# brush.net
KiCad netlist of a schematic drawn in EAGLE
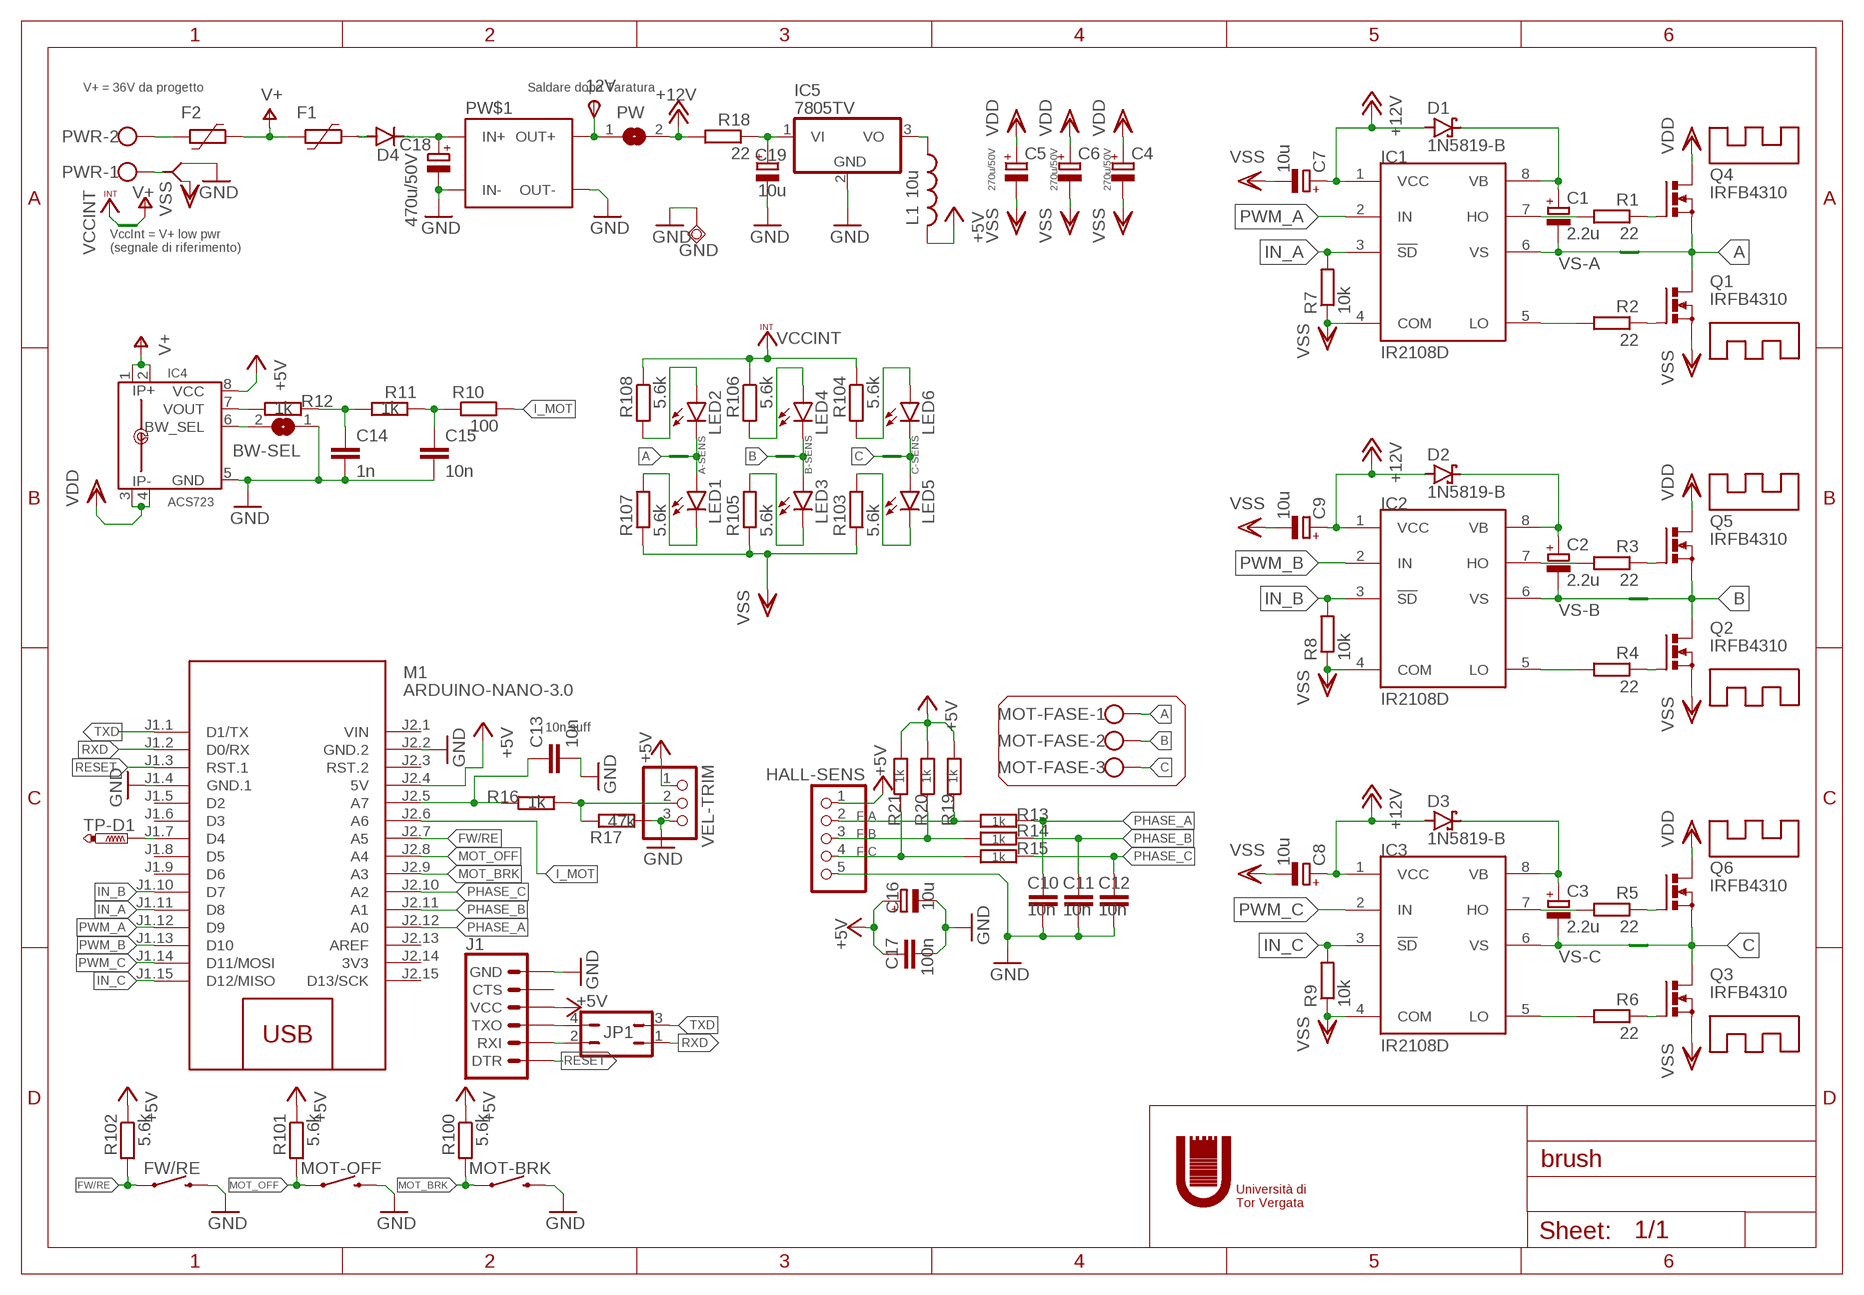
[diagram p0: schematic, sheet 1]

(export (version "E")
  (design (tool "Eeschema 10.0.6"))
  (components
    (comp (ref "12V")
      (value "TPSPAD1-13")
      (footprint "eagle-import:P1-13")
      (libsource (lib "eagle-import") (part "TPSPAD1-13"))
    )
    (comp (ref "BW-SEL")
      (value "SJ")
      (footprint "eagle-import:SJ")
      (libsource (lib "eagle-import") (part "SJ"))
    )
    (comp (ref "C1")
      (value "2.2u")
      (footprint "eagle-import:E5-6")
      (libsource (lib "eagle-import") (part "CPOL-EUE5-6"))
    )
    (comp (ref "C2")
      (value "2.2u")
      (footprint "eagle-import:E5-6")
      (libsource (lib "eagle-import") (part "CPOL-EUE5-6"))
    )
    (comp (ref "C3")
      (value "2.2u")
      (footprint "eagle-import:E5-6")
      (libsource (lib "eagle-import") (part "CPOL-EUE5-6"))
    )
    (comp (ref "C4")
      (value "270u/50V")
      (footprint "eagle-import:E7,5-18")
      (libsource (lib "eagle-import") (part "CPOL-EUE7.5-18"))
    )
    (comp (ref "C5")
      (value "270u/50V")
      (footprint "eagle-import:E7,5-18")
      (libsource (lib "eagle-import") (part "CPOL-EUE7.5-18"))
    )
    (comp (ref "C6")
      (value "270u/50V")
      (footprint "eagle-import:E7,5-18")
      (libsource (lib "eagle-import") (part "CPOL-EUE7.5-18"))
    )
    (comp (ref "C7")
      (value "10u")
      (footprint "eagle-import:E5-6")
      (libsource (lib "eagle-import") (part "CPOL-EUE5-6"))
    )
    (comp (ref "C8")
      (value "10u")
      (footprint "eagle-import:E5-6")
      (libsource (lib "eagle-import") (part "CPOL-EUE5-6"))
    )
    (comp (ref "C9")
      (value "10u")
      (footprint "eagle-import:E5-6")
      (libsource (lib "eagle-import") (part "CPOL-EUE5-6"))
    )
    (comp (ref "C10")
      (value "10n")
      (footprint "eagle-import:C025-025X050")
      (libsource (lib "eagle-import") (part "C-EU025-025X050"))
    )
    (comp (ref "C11")
      (value "10n")
      (footprint "eagle-import:C025-025X050")
      (libsource (lib "eagle-import") (part "C-EU025-025X050"))
    )
    (comp (ref "C12")
      (value "10n")
      (footprint "eagle-import:C025-025X050")
      (libsource (lib "eagle-import") (part "C-EU025-025X050"))
    )
    (comp (ref "C13")
      (value "10n")
      (footprint "eagle-import:C025-025X050")
      (libsource (lib "eagle-import") (part "C-EU025-025X050"))
    )
    (comp (ref "C14")
      (value "1n")
      (footprint "eagle-import:C025-025X050")
      (libsource (lib "eagle-import") (part "C-EU025-025X050"))
    )
    (comp (ref "C15")
      (value "10n")
      (footprint "eagle-import:C025-025X050")
      (libsource (lib "eagle-import") (part "C-EU025-025X050"))
    )
    (comp (ref "C16")
      (value "10u")
      (footprint "eagle-import:E5-6")
      (libsource (lib "eagle-import") (part "CPOL-EUE5-6"))
    )
    (comp (ref "C17")
      (value "100n")
      (footprint "eagle-import:C025-025X050")
      (libsource (lib "eagle-import") (part "C-EU025-025X050"))
    )
    (comp (ref "C18")
      (value "470u/50V")
      (footprint "eagle-import:E5-13")
      (libsource (lib "eagle-import") (part "CPOL-EUE5-13"))
    )
    (comp (ref "C19")
      (value "10u")
      (footprint "eagle-import:E5-6")
      (libsource (lib "eagle-import") (part "CPOL-EUE5-6"))
    )
    (comp (ref "D1")
      (value "1N5819-B")
      (footprint "eagle-import:DO41-7.6")
      (libsource (lib "eagle-import") (part "1N5819-B"))
    )
    (comp (ref "D2")
      (value "1N5819-B")
      (footprint "eagle-import:DO41-7.6")
      (libsource (lib "eagle-import") (part "1N5819-B"))
    )
    (comp (ref "D3")
      (value "1N5819-B")
      (footprint "eagle-import:DO41-7.6")
      (libsource (lib "eagle-import") (part "1N5819-B"))
    )
    (comp (ref "D4")
      (value "ES2D")
      (footprint "eagle-import:SMB")
      (libsource (lib "eagle-import") (part "ES2D"))
    )
    (comp (ref "F1")
      (value "2410-BOX")
      (footprint "eagle-import:BELFUSE0679-3000-12")
      (libsource (lib "eagle-import") (part "?2410-BOX"))
    )
    (comp (ref "F2")
      (value "2410-BOX")
      (footprint "eagle-import:BELFUSE0679-3000-12")
      (libsource (lib "eagle-import") (part "?2410-BOX"))
    )
    (comp (ref "FW/RE")
      (value "MOMENTARY-SWITCH-SPST-PTH-6.0MM")
      (footprint "eagle-import:TACTILE_SWITCH_PTH_6.0MM")
      (libsource (lib "eagle-import") (part "MOMENTARY-SWITCH-SPST-PTH-6.0MM"))
    )
    (comp (ref "GND")
      (value "TPSQPAD1-13")
      (footprint "eagle-import:P1-13")
      (libsource (lib "eagle-import") (part "TPSQPAD1-13"))
    )
    (comp (ref "HALL-SENS")
      (value "PINHD-1X5")
      (footprint "eagle-import:1X05")
      (libsource (lib "eagle-import") (part "PINHD-1X5"))
    )
    (comp (ref "IC1")
      (value "IR2108D")
      (footprint "eagle-import:DIL08")
      (libsource (lib "eagle-import") (part "IR2108D"))
    )
    (comp (ref "IC2")
      (value "IR2108D")
      (footprint "eagle-import:DIL08")
      (libsource (lib "eagle-import") (part "IR2108D"))
    )
    (comp (ref "IC3")
      (value "IR2108D")
      (footprint "eagle-import:DIL08")
      (libsource (lib "eagle-import") (part "IR2108D"))
    )
    (comp (ref "IC4")
      (value "ACS723")
      (footprint "eagle-import:SOIC8")
      (libsource (lib "eagle-import") (part "ACS723"))
    )
    (comp (ref "IC5")
      (value "7805TV")
      (footprint "eagle-import:TO220V")
      (libsource (lib "eagle-import") (part "78TV05"))
    )
    (comp (ref "J1")
      (value "6_PIN_SERIAL_TARGETSILK")
      (footprint "eagle-import:6_PIN_SERIAL_TARGET_SIDE_W_SILK")
      (libsource (lib "eagle-import") (part "6_PIN_SERIAL_TARGETSILK"))
    )
    (comp (ref "JP1")
      (value "JP2Q")
      (footprint "eagle-import:JP2Q")
      (libsource (lib "eagle-import") (part "JP2Q"))
    )
    (comp (ref "L1")
      (value "10u")
      (footprint "eagle-import:0207_5V")
      (libsource (lib "eagle-import") (part "L-US0207/5V"))
    )
    (comp (ref "LED1")
      (value "LED3MM")
      (footprint "eagle-import:LED3MM")
      (libsource (lib "eagle-import") (part "LED3MM"))
    )
    (comp (ref "LED2")
      (value "LED3MM")
      (footprint "eagle-import:LED3MM")
      (libsource (lib "eagle-import") (part "LED3MM"))
    )
    (comp (ref "LED3")
      (value "LED3MM")
      (footprint "eagle-import:LED3MM")
      (libsource (lib "eagle-import") (part "LED3MM"))
    )
    (comp (ref "LED4")
      (value "LED3MM")
      (footprint "eagle-import:LED3MM")
      (libsource (lib "eagle-import") (part "LED3MM"))
    )
    (comp (ref "LED5")
      (value "LED3MM")
      (footprint "eagle-import:LED3MM")
      (libsource (lib "eagle-import") (part "LED3MM"))
    )
    (comp (ref "LED6")
      (value "LED3MM")
      (footprint "eagle-import:LED3MM")
      (libsource (lib "eagle-import") (part "LED3MM"))
    )
    (comp (ref "M1")
      (value "ARDUINO-NANO-3.0")
      (footprint "eagle-import:ARDUINO-NANO-3.0")
      (libsource (lib "eagle-import") (part "ARDUINO-NANO-3.0"))
    )
    (comp (ref "MOT-BRK")
      (value "MOMENTARY-SWITCH-SPST-PTH-6.0MM")
      (footprint "eagle-import:TACTILE_SWITCH_PTH_6.0MM")
      (libsource (lib "eagle-import") (part "MOMENTARY-SWITCH-SPST-PTH-6.0MM"))
    )
    (comp (ref "MOT-FASE")
      (value "W237-103")
      (footprint "eagle-import:W237-103")
      (fields (field (name "MPN") "237-103"))
      (libsource (lib "eagle-import") (part "W237-103"))
    )
    (comp (ref "MOT-OFF")
      (value "MOMENTARY-SWITCH-SPST-PTH-6.0MM")
      (footprint "eagle-import:TACTILE_SWITCH_PTH_6.0MM")
      (libsource (lib "eagle-import") (part "MOMENTARY-SWITCH-SPST-PTH-6.0MM"))
    )
    (comp (ref "PW") (value "SJ") (footprint "eagle-import:SJ") (libsource (lib "eagle-import") (part "SJ")))
    (comp (ref "PW$1")
      (value "DC/DC-STEP-DOWNOLD-ALFY")
      (footprint "eagle-import:DC-DC-STEP-DOWN-LM2596-ALFY")
      (libsource (lib "eagle-import") (part "DC/DC-STEP-DOWNOLD-ALFY"))
    )
    (comp (ref "PWR")
      (value "W237-102")
      (footprint "eagle-import:W237-102")
      (fields (field (name "MPN") "237-102"))
      (libsource (lib "eagle-import") (part "W237-102"))
    )
    (comp (ref "Q1")
      (value "IRFB4310")
      (footprint "eagle-import:TO220BV")
      (libsource (lib "eagle-import") (part "PMOSFET_NTO220BV"))
    )
    (comp (ref "Q2")
      (value "IRFB4310")
      (footprint "eagle-import:TO220BV")
      (libsource (lib "eagle-import") (part "PMOSFET_NTO220BV"))
    )
    (comp (ref "Q3")
      (value "IRFB4310")
      (footprint "eagle-import:TO220BV")
      (libsource (lib "eagle-import") (part "PMOSFET_NTO220BV"))
    )
    (comp (ref "Q4")
      (value "IRFB4310")
      (footprint "eagle-import:TO220BV")
      (libsource (lib "eagle-import") (part "PMOSFET_NTO220BV"))
    )
    (comp (ref "Q5")
      (value "IRFB4310")
      (footprint "eagle-import:TO220BV")
      (libsource (lib "eagle-import") (part "PMOSFET_NTO220BV"))
    )
    (comp (ref "Q6")
      (value "IRFB4310")
      (footprint "eagle-import:TO220BV")
      (libsource (lib "eagle-import") (part "PMOSFET_NTO220BV"))
    )
    (comp (ref "R1")
      (value "22")
      (footprint "eagle-import:R1206")
      (libsource (lib "eagle-import") (part "R-EU_R1206"))
    )
    (comp (ref "R2")
      (value "22")
      (footprint "eagle-import:R1206")
      (libsource (lib "eagle-import") (part "R-EU_R1206"))
    )
    (comp (ref "R3")
      (value "22")
      (footprint "eagle-import:R1206")
      (libsource (lib "eagle-import") (part "R-EU_R1206"))
    )
    (comp (ref "R4")
      (value "22")
      (footprint "eagle-import:R1206")
      (libsource (lib "eagle-import") (part "R-EU_R1206"))
    )
    (comp (ref "R5")
      (value "22")
      (footprint "eagle-import:R1206")
      (libsource (lib "eagle-import") (part "R-EU_R1206"))
    )
    (comp (ref "R6")
      (value "22")
      (footprint "eagle-import:R1206")
      (libsource (lib "eagle-import") (part "R-EU_R1206"))
    )
    (comp (ref "R7")
      (value "10k")
      (footprint "eagle-import:R1206")
      (libsource (lib "eagle-import") (part "R-EU_R1206"))
    )
    (comp (ref "R8")
      (value "10k")
      (footprint "eagle-import:R1206")
      (libsource (lib "eagle-import") (part "R-EU_R1206"))
    )
    (comp (ref "R9")
      (value "10k")
      (footprint "eagle-import:R1206")
      (libsource (lib "eagle-import") (part "R-EU_R1206"))
    )
    (comp (ref "R10")
      (value "100")
      (footprint "eagle-import:R1206")
      (libsource (lib "eagle-import") (part "R-EU_R1206"))
    )
    (comp (ref "R11")
      (value "1k")
      (footprint "eagle-import:R1206")
      (libsource (lib "eagle-import") (part "R-EU_R1206"))
    )
    (comp (ref "R12")
      (value "1k")
      (footprint "eagle-import:R1206")
      (libsource (lib "eagle-import") (part "R-EU_R1206"))
    )
    (comp (ref "R13")
      (value "1k")
      (footprint "eagle-import:R1206")
      (libsource (lib "eagle-import") (part "R-EU_R1206"))
    )
    (comp (ref "R14")
      (value "1k")
      (footprint "eagle-import:R1206")
      (libsource (lib "eagle-import") (part "R-EU_R1206"))
    )
    (comp (ref "R15")
      (value "1k")
      (footprint "eagle-import:R1206")
      (libsource (lib "eagle-import") (part "R-EU_R1206"))
    )
    (comp (ref "R16")
      (value "1k")
      (footprint "eagle-import:R1206")
      (libsource (lib "eagle-import") (part "R-EU_R1206"))
    )
    (comp (ref "R17")
      (value "47k")
      (footprint "eagle-import:R1206")
      (libsource (lib "eagle-import") (part "R-EU_R1206"))
    )
    (comp (ref "R18")
      (value "22")
      (footprint "eagle-import:0204_7")
      (libsource (lib "eagle-import") (part "R-EU_0204/7"))
    )
    (comp (ref "R19")
      (value "1k")
      (footprint "eagle-import:R1206")
      (libsource (lib "eagle-import") (part "R-EU_R1206"))
    )
    (comp (ref "R20")
      (value "1k")
      (footprint "eagle-import:R1206")
      (libsource (lib "eagle-import") (part "R-EU_R1206"))
    )
    (comp (ref "R21")
      (value "1k")
      (footprint "eagle-import:R1206")
      (libsource (lib "eagle-import") (part "R-EU_R1206"))
    )
    (comp (ref "R100")
      (value "5.6k")
      (footprint "eagle-import:R1206")
      (libsource (lib "eagle-import") (part "R-EU_R1206"))
    )
    (comp (ref "R101")
      (value "5.6k")
      (footprint "eagle-import:R1206")
      (libsource (lib "eagle-import") (part "R-EU_R1206"))
    )
    (comp (ref "R102")
      (value "5.6k")
      (footprint "eagle-import:R1206")
      (libsource (lib "eagle-import") (part "R-EU_R1206"))
    )
    (comp (ref "R103")
      (value "5.6k")
      (footprint "eagle-import:R1206")
      (libsource (lib "eagle-import") (part "R-EU_R1206"))
    )
    (comp (ref "R104")
      (value "5.6k")
      (footprint "eagle-import:R1206")
      (libsource (lib "eagle-import") (part "R-EU_R1206"))
    )
    (comp (ref "R105")
      (value "5.6k")
      (footprint "eagle-import:R1206")
      (libsource (lib "eagle-import") (part "R-EU_R1206"))
    )
    (comp (ref "R106")
      (value "5.6k")
      (footprint "eagle-import:R1206")
      (libsource (lib "eagle-import") (part "R-EU_R1206"))
    )
    (comp (ref "R107")
      (value "5.6k")
      (footprint "eagle-import:R1206")
      (libsource (lib "eagle-import") (part "R-EU_R1206"))
    )
    (comp (ref "R108")
      (value "5.6k")
      (footprint "eagle-import:R1206")
      (libsource (lib "eagle-import") (part "R-EU_R1206"))
    )
    (comp (ref "TP-D1")
      (value "PTR1PAD1-17")
      (footprint "eagle-import:P1-17")
      (libsource (lib "eagle-import") (part "PTR1PAD1-17"))
    )
    (comp (ref "U$1")
      (value "NET12X12")
      (footprint "eagle-import:NET-NET_12X12MIL")
      (libsource (lib "eagle-import") (part "NET12X12"))
    )
    (comp (ref "U$2")
      (value "NET12X12")
      (footprint "eagle-import:NET-NET_12X12MIL")
      (libsource (lib "eagle-import") (part "NET12X12"))
    )
    (comp (ref "U$3")
      (value "DISSTO-220")
      (footprint "eagle-import:TO-220")
      (libsource (lib "eagle-import") (part "DISSTO-220"))
    )
    (comp (ref "U$4")
      (value "DISSTO-220")
      (footprint "eagle-import:TO-220")
      (libsource (lib "eagle-import") (part "DISSTO-220"))
    )
    (comp (ref "U$6")
      (value "NET12X12")
      (footprint "eagle-import:NET-NET_12X12MIL")
      (libsource (lib "eagle-import") (part "NET12X12"))
    )
    (comp (ref "U$7")
      (value "DISSTO-220")
      (footprint "eagle-import:TO-220")
      (libsource (lib "eagle-import") (part "DISSTO-220"))
    )
    (comp (ref "U$8")
      (value "DISSTO-220")
      (footprint "eagle-import:TO-220")
      (libsource (lib "eagle-import") (part "DISSTO-220"))
    )
    (comp (ref "U$9")
      (value "DISSTO-220")
      (footprint "eagle-import:TO-220")
      (libsource (lib "eagle-import") (part "DISSTO-220"))
    )
    (comp (ref "U$10")
      (value "DISSTO-220")
      (footprint "eagle-import:TO-220")
      (libsource (lib "eagle-import") (part "DISSTO-220"))
    )
    (comp (ref "U$11")
      (value "NET12X12")
      (footprint "eagle-import:NET-NET_12X12MIL")
      (libsource (lib "eagle-import") (part "NET12X12"))
    )
    (comp (ref "U$12")
      (value "NET12X12")
      (footprint "eagle-import:NET-NET_12X12MIL")
      (libsource (lib "eagle-import") (part "NET12X12"))
    )
    (comp (ref "U$13")
      (value "NET12X12")
      (footprint "eagle-import:NET-NET_12X12MIL")
      (libsource (lib "eagle-import") (part "NET12X12"))
    )
    (comp (ref "U$14")
      (value "NET12X12")
      (footprint "eagle-import:NET-NET_12X12MIL")
      (libsource (lib "eagle-import") (part "NET12X12"))
    )
    (comp (ref "U$100")
      (value "3NET25X50MIL")
      (footprint "eagle-import:3NET-25X50MIL")
      (libsource (lib "eagle-import") (part "3NET25X50MIL"))
    )
    (comp (ref "VEL-TRIM")
      (value "PINHD-1X3")
      (footprint "eagle-import:1X03")
      (libsource (lib "eagle-import") (part "PINHD-1X3"))
    )
  )
  (nets
    (net (code "1") (name "+5V") (class "Default")
      (node (ref "C16") (pin "+") (pinfunction "+_+") (pintype "passive"))
      (node (ref "C17") (pin "1") (pinfunction "1_1") (pintype "passive"))
      (node (ref "HALL-SENS") (pin "1") (pinfunction "1_1") (pintype "passive"))
      (node (ref "IC4") (pin "8") (pinfunction "VCC_8") (pintype "power_in"))
      (node (ref "J1") (pin "P$4") (pinfunction "VCC_P$4") (pintype "passive"))
      (node (ref "L1") (pin "2") (pinfunction "2_2") (pintype "passive"))
      (node (ref "M1") (pin "J2.4") (pinfunction "5V_J2.4") (pintype "power_in"))
      (node (ref "R100") (pin "1") (pinfunction "1_1") (pintype "passive"))
      (node (ref "R101") (pin "1") (pinfunction "1_1") (pintype "passive"))
      (node (ref "R102") (pin "1") (pinfunction "1_1") (pintype "passive"))
      (node (ref "R19") (pin "2") (pinfunction "2_2") (pintype "passive"))
      (node (ref "R20") (pin "2") (pinfunction "2_2") (pintype "passive"))
      (node (ref "R21") (pin "2") (pinfunction "2_2") (pintype "passive"))
      (node (ref "VEL-TRIM") (pin "1") (pinfunction "1_1") (pintype "passive"))
    )
    (net (code "2") (name "+12V") (class "Default")
      (node (ref "C7") (pin "+") (pinfunction "+_+") (pintype "passive"))
      (node (ref "C8") (pin "+") (pinfunction "+_+") (pintype "passive"))
      (node (ref "C9") (pin "+") (pinfunction "+_+") (pintype "passive"))
      (node (ref "D1") (pin "A") (pinfunction "A_A") (pintype "passive"))
      (node (ref "D2") (pin "A") (pinfunction "A_A") (pintype "passive"))
      (node (ref "D3") (pin "A") (pinfunction "A_A") (pintype "passive"))
      (node (ref "IC1") (pin "1") (pinfunction "VCC_1") (pintype "power_in"))
      (node (ref "IC2") (pin "1") (pinfunction "VCC_1") (pintype "power_in"))
      (node (ref "IC3") (pin "1") (pinfunction "VCC_1") (pintype "power_in"))
      (node (ref "PW") (pin "2") (pinfunction "2_2") (pintype "passive"))
      (node (ref "R18") (pin "2") (pinfunction "2_2") (pintype "passive"))
    )
    (net (code "3") (name "/3V3") (class "Default")
      (node (ref "M1") (pin "J2.14") (pinfunction "3V3_J2.14") (pintype "power_in"))
    )
    (net (code "4") (name "/A-SENS") (class "Default")
      (node (ref "LED1") (pin "A") (pinfunction "A_A") (pintype "passive"))
      (node (ref "LED2") (pin "K") (pinfunction "C_K") (pintype "passive"))
      (node (ref "U$1") (pin "N1") (pinfunction "P$1_N1") (pintype "bidirectional"))
    )
    (net (code "5") (name "/B-SENS") (class "Default")
      (node (ref "LED3") (pin "A") (pinfunction "A_A") (pintype "passive"))
      (node (ref "LED4") (pin "K") (pinfunction "C_K") (pintype "passive"))
      (node (ref "U$2") (pin "N1") (pinfunction "P$1_N1") (pintype "bidirectional"))
    )
    (net (code "6") (name "/C-SENS") (class "Default")
      (node (ref "LED5") (pin "A") (pinfunction "A_A") (pintype "passive"))
      (node (ref "LED6") (pin "K") (pinfunction "C_K") (pintype "passive"))
      (node (ref "U$6") (pin "N1") (pinfunction "P$1_N1") (pintype "bidirectional"))
    )
    (net (code "7") (name "/F-A") (class "Default")
      (node (ref "HALL-SENS") (pin "2") (pinfunction "2_2") (pintype "passive"))
      (node (ref "R13") (pin "2") (pinfunction "2_2") (pintype "passive"))
      (node (ref "R19") (pin "1") (pinfunction "1_1") (pintype "passive"))
    )
    (net (code "8") (name "/F-B") (class "Default")
      (node (ref "HALL-SENS") (pin "3") (pinfunction "3_3") (pintype "passive"))
      (node (ref "R14") (pin "2") (pinfunction "2_2") (pintype "passive"))
      (node (ref "R20") (pin "1") (pinfunction "1_1") (pintype "passive"))
    )
    (net (code "9") (name "/F-C") (class "Default")
      (node (ref "HALL-SENS") (pin "4") (pinfunction "4_4") (pintype "passive"))
      (node (ref "R15") (pin "2") (pinfunction "2_2") (pintype "passive"))
      (node (ref "R21") (pin "1") (pinfunction "1_1") (pintype "passive"))
    )
    (net (code "10") (name "/VIN") (class "Default")
      (node (ref "M1") (pin "J2.1") (pinfunction "VIN_J2.1") (pintype "power_in"))
    )
    (net (code "11") (name "/VS-A") (class "Default")
      (node (ref "C1") (pin "-") (pinfunction "-_-") (pintype "passive"))
      (node (ref "IC1") (pin "6") (pinfunction "VS_6") (pintype "power_in"))
      (node (ref "U$11") (pin "N1") (pinfunction "P$1_N1") (pintype "bidirectional"))
    )
    (net (code "12") (name "/VS-B") (class "Default")
      (node (ref "C2") (pin "-") (pinfunction "-_-") (pintype "passive"))
      (node (ref "IC2") (pin "6") (pinfunction "VS_6") (pintype "power_in"))
      (node (ref "U$13") (pin "N1") (pinfunction "P$1_N1") (pintype "bidirectional"))
    )
    (net (code "13") (name "/VS-C") (class "Default")
      (node (ref "C3") (pin "-") (pinfunction "-_-") (pintype "passive"))
      (node (ref "IC3") (pin "6") (pinfunction "VS_6") (pintype "power_in"))
      (node (ref "U$12") (pin "N1") (pinfunction "P$1_N1") (pintype "bidirectional"))
    )
    (net (code "14") (name "A") (class "Default")
      (node (ref "MOT-FASE") (pin "1") (pinfunction "KL_1") (pintype "passive"))
      (node (ref "Q1") (pin "D") (pinfunction "D_D") (pintype "passive"))
      (node (ref "Q4") (pin "S") (pinfunction "S_S") (pintype "passive"))
      (node (ref "U$1") (pin "N2") (pinfunction "P$2_N2") (pintype "bidirectional"))
      (node (ref "U$11") (pin "N2") (pinfunction "P$2_N2") (pintype "bidirectional"))
    )
    (net (code "15") (name "B") (class "Default")
      (node (ref "MOT-FASE") (pin "2") (pinfunction "KL_2") (pintype "passive"))
      (node (ref "Q2") (pin "D") (pinfunction "D_D") (pintype "passive"))
      (node (ref "Q5") (pin "S") (pinfunction "S_S") (pintype "passive"))
      (node (ref "U$13") (pin "N2") (pinfunction "P$2_N2") (pintype "bidirectional"))
      (node (ref "U$2") (pin "N2") (pinfunction "P$2_N2") (pintype "bidirectional"))
    )
    (net (code "16") (name "C") (class "Default")
      (node (ref "MOT-FASE") (pin "3") (pinfunction "KL_3") (pintype "passive"))
      (node (ref "Q3") (pin "D") (pinfunction "D_D") (pintype "passive"))
      (node (ref "Q6") (pin "S") (pinfunction "S_S") (pintype "passive"))
      (node (ref "U$12") (pin "N2") (pinfunction "P$2_N2") (pintype "bidirectional"))
      (node (ref "U$6") (pin "N2") (pinfunction "P$2_N2") (pintype "bidirectional"))
    )
    (net (code "17") (name "FW{slash}RE") (class "Default")
      (node (ref "FW/RE") (pin "1") (pinfunction "1_1") (pintype "passive"))
      (node (ref "M1") (pin "J2.7") (pinfunction "A5_J2.7") (pintype "bidirectional"))
      (node (ref "R102") (pin "2") (pinfunction "2_2") (pintype "passive"))
    )
    (net (code "18") (name "GND") (class "Default")
      (node (ref "BW-SEL") (pin "1") (pinfunction "1_1") (pintype "passive"))
      (node (ref "C10") (pin "2") (pinfunction "2_2") (pintype "passive"))
      (node (ref "C11") (pin "2") (pinfunction "2_2") (pintype "passive"))
      (node (ref "C12") (pin "2") (pinfunction "2_2") (pintype "passive"))
      (node (ref "C13") (pin "2") (pinfunction "2_2") (pintype "passive"))
      (node (ref "C14") (pin "2") (pinfunction "2_2") (pintype "passive"))
      (node (ref "C15") (pin "2") (pinfunction "2_2") (pintype "passive"))
      (node (ref "C16") (pin "-") (pinfunction "-_-") (pintype "passive"))
      (node (ref "C17") (pin "2") (pinfunction "2_2") (pintype "passive"))
      (node (ref "C18") (pin "-") (pinfunction "-_-") (pintype "passive"))
      (node (ref "C19") (pin "-") (pinfunction "-_-") (pintype "passive"))
      (node (ref "FW/RE") (pin "3") (pinfunction "2_3") (pintype "passive"))
      (node (ref "GND") (pin "TP") (pinfunction "TP_TP") (pintype "input"))
      (node (ref "HALL-SENS") (pin "5") (pinfunction "5_5") (pintype "passive"))
      (node (ref "IC4") (pin "5") (pinfunction "GND_5") (pintype "power_in"))
      (node (ref "IC5") (pin "2") (pinfunction "GND_2") (pintype "passive"))
      (node (ref "J1") (pin "P$6") (pinfunction "GND_P$6") (pintype "passive"))
      (node (ref "M1") (pin "J1.4") (pinfunction "GND.1_J1.4") (pintype "power_in"))
      (node (ref "M1") (pin "J2.2") (pinfunction "GND.2_J2.2") (pintype "power_in"))
      (node (ref "MOT-BRK") (pin "3") (pinfunction "2_3") (pintype "passive"))
      (node (ref "MOT-OFF") (pin "3") (pinfunction "2_3") (pintype "passive"))
      (node (ref "PW$1") (pin "IN-") (pinfunction "IN-_IN-") (pintype "bidirectional"))
      (node (ref "PW$1") (pin "OUT-") (pinfunction "OUT-_OUT-") (pintype "bidirectional"))
      (node (ref "R17") (pin "2") (pinfunction "2_2") (pintype "passive"))
      (node (ref "U$100") (pin "S2") (pinfunction "S2_S2") (pintype "bidirectional"))
      (node (ref "VEL-TRIM") (pin "3") (pinfunction "3_3") (pintype "passive"))
    )
    (net (code "19") (name "IN_A") (class "Default")
      (node (ref "IC1") (pin "3") (pinfunction "~{SD}_3") (pintype "input"))
      (node (ref "M1") (pin "J1.11") (pinfunction "D8_J1.11") (pintype "bidirectional"))
      (node (ref "R7") (pin "2") (pinfunction "2_2") (pintype "passive"))
    )
    (net (code "20") (name "IN_B") (class "Default")
      (node (ref "IC2") (pin "3") (pinfunction "~{SD}_3") (pintype "input"))
      (node (ref "M1") (pin "J1.10") (pinfunction "D7_J1.10") (pintype "bidirectional"))
      (node (ref "R8") (pin "2") (pinfunction "2_2") (pintype "passive"))
    )
    (net (code "21") (name "IN_C") (class "Default")
      (node (ref "IC3") (pin "3") (pinfunction "~{SD}_3") (pintype "input"))
      (node (ref "M1") (pin "J1.15") (pinfunction "D12/MISO_J1.15") (pintype "bidirectional"))
      (node (ref "R9") (pin "2") (pinfunction "2_2") (pintype "passive"))
    )
    (net (code "22") (name "I_MOT") (class "Default")
      (node (ref "M1") (pin "J2.6") (pinfunction "A6_J2.6") (pintype "bidirectional"))
      (node (ref "R10") (pin "2") (pinfunction "2_2") (pintype "passive"))
    )
    (net (code "23") (name "MOT_BRK") (class "Default")
      (node (ref "M1") (pin "J2.9") (pinfunction "A3_J2.9") (pintype "bidirectional"))
      (node (ref "MOT-BRK") (pin "1") (pinfunction "1_1") (pintype "passive"))
      (node (ref "R100") (pin "2") (pinfunction "2_2") (pintype "passive"))
    )
    (net (code "24") (name "MOT_OFF") (class "Default")
      (node (ref "M1") (pin "J2.8") (pinfunction "A4_J2.8") (pintype "bidirectional"))
      (node (ref "MOT-OFF") (pin "1") (pinfunction "1_1") (pintype "passive"))
      (node (ref "R101") (pin "2") (pinfunction "2_2") (pintype "passive"))
    )
    (net (code "25") (name "Net-(12V-PP)") (class "Default")
      (node (ref "12V") (pin "TP") (pinfunction "PP_TP") (pintype "input"))
      (node (ref "PW") (pin "1") (pinfunction "1_1") (pintype "passive"))
      (node (ref "PW$1") (pin "OUT+") (pinfunction "OUT+_OUT+") (pintype "bidirectional"))
    )
    (net (code "26") (name "Net-(C14-Pad1)") (class "Default")
      (node (ref "C14") (pin "1") (pinfunction "1_1") (pintype "passive"))
      (node (ref "R11") (pin "2") (pinfunction "2_2") (pintype "passive"))
      (node (ref "R12") (pin "1") (pinfunction "1_1") (pintype "passive"))
    )
    (net (code "27") (name "Net-(C15-Pad1)") (class "Default")
      (node (ref "C15") (pin "1") (pinfunction "1_1") (pintype "passive"))
      (node (ref "R10") (pin "1") (pinfunction "1_1") (pintype "passive"))
      (node (ref "R11") (pin "1") (pinfunction "1_1") (pintype "passive"))
    )
    (net (code "28") (name "Net-(C18-Pad+)") (class "Default")
      (node (ref "C18") (pin "+") (pinfunction "+_+") (pintype "passive"))
      (node (ref "D4") (pin "C") (pinfunction "C_C") (pintype "passive"))
      (node (ref "PW$1") (pin "IN+") (pinfunction "IN+_IN+") (pintype "bidirectional"))
    )
    (net (code "29") (name "Net-(D4-PadA)") (class "Default")
      (node (ref "D4") (pin "A") (pinfunction "A_A") (pintype "passive"))
      (node (ref "F1") (pin "1") (pinfunction "1_1") (pintype "passive"))
    )
    (net (code "30") (name "Net-(IC1-HO)") (class "Default")
      (node (ref "IC1") (pin "7") (pinfunction "HO_7") (pintype "output"))
      (node (ref "R1") (pin "2") (pinfunction "2_2") (pintype "passive"))
    )
    (net (code "31") (name "Net-(IC1-LO)") (class "Default")
      (node (ref "IC1") (pin "5") (pinfunction "LO_5") (pintype "output"))
      (node (ref "R2") (pin "2") (pinfunction "2_2") (pintype "passive"))
    )
    (net (code "32") (name "Net-(IC1-VB)") (class "Default")
      (node (ref "C1") (pin "+") (pinfunction "+_+") (pintype "passive"))
      (node (ref "D1") (pin "C") (pinfunction "C_C") (pintype "passive"))
      (node (ref "IC1") (pin "8") (pinfunction "VB_8") (pintype "power_in"))
    )
    (net (code "33") (name "Net-(IC2-HO)") (class "Default")
      (node (ref "IC2") (pin "7") (pinfunction "HO_7") (pintype "output"))
      (node (ref "R3") (pin "2") (pinfunction "2_2") (pintype "passive"))
    )
    (net (code "34") (name "Net-(IC2-LO)") (class "Default")
      (node (ref "IC2") (pin "5") (pinfunction "LO_5") (pintype "output"))
      (node (ref "R4") (pin "2") (pinfunction "2_2") (pintype "passive"))
    )
    (net (code "35") (name "Net-(IC2-VB)") (class "Default")
      (node (ref "C2") (pin "+") (pinfunction "+_+") (pintype "passive"))
      (node (ref "D2") (pin "C") (pinfunction "C_C") (pintype "passive"))
      (node (ref "IC2") (pin "8") (pinfunction "VB_8") (pintype "power_in"))
    )
    (net (code "36") (name "Net-(IC3-HO)") (class "Default")
      (node (ref "IC3") (pin "7") (pinfunction "HO_7") (pintype "output"))
      (node (ref "R5") (pin "2") (pinfunction "2_2") (pintype "passive"))
    )
    (net (code "37") (name "Net-(IC3-LO)") (class "Default")
      (node (ref "IC3") (pin "5") (pinfunction "LO_5") (pintype "output"))
      (node (ref "R6") (pin "2") (pinfunction "2_2") (pintype "passive"))
    )
    (net (code "38") (name "Net-(IC3-VB)") (class "Default")
      (node (ref "C3") (pin "+") (pinfunction "+_+") (pintype "passive"))
      (node (ref "D3") (pin "C") (pinfunction "C_C") (pintype "passive"))
      (node (ref "IC3") (pin "8") (pinfunction "VB_8") (pintype "power_in"))
    )
    (net (code "39") (name "Net-(IC4-BW_SEL)") (class "Default")
      (node (ref "BW-SEL") (pin "2") (pinfunction "2_2") (pintype "passive"))
      (node (ref "IC4") (pin "6") (pinfunction "BW_SEL_6") (pintype "bidirectional"))
    )
    (net (code "40") (name "Net-(IC4-VOUT)") (class "Default")
      (node (ref "IC4") (pin "7") (pinfunction "VOUT_7") (pintype "output"))
      (node (ref "R12") (pin "2") (pinfunction "2_2") (pintype "passive"))
    )
    (net (code "41") (name "Net-(IC5-VI)") (class "Default")
      (node (ref "C19") (pin "+") (pinfunction "+_+") (pintype "passive"))
      (node (ref "IC5") (pin "1") (pinfunction "VI_1") (pintype "input"))
      (node (ref "R18") (pin "1") (pinfunction "1_1") (pintype "passive"))
    )
    (net (code "42") (name "Net-(IC5-VO)") (class "Default")
      (node (ref "IC5") (pin "3") (pinfunction "VO_3") (pintype "passive"))
      (node (ref "L1") (pin "1") (pinfunction "1_1") (pintype "passive"))
    )
    (net (code "43") (name "Net-(J1-RXI)") (class "Default")
      (node (ref "J1") (pin "P$3") (pinfunction "RXI_P$3") (pintype "passive"))
      (node (ref "JP1") (pin "2") (pinfunction "2_2") (pintype "passive"))
    )
    (net (code "44") (name "Net-(J1-TXO)") (class "Default")
      (node (ref "J1") (pin "P$2") (pinfunction "TXO_P$2") (pintype "passive"))
      (node (ref "JP1") (pin "4") (pinfunction "4_4") (pintype "passive"))
    )
    (net (code "45") (name "Net-(LED1-C)") (class "Default")
      (node (ref "LED1") (pin "K") (pinfunction "C_K") (pintype "passive"))
      (node (ref "R107") (pin "2") (pinfunction "2_2") (pintype "passive"))
    )
    (net (code "46") (name "Net-(LED2-PadA)") (class "Default")
      (node (ref "LED2") (pin "A") (pinfunction "A_A") (pintype "passive"))
      (node (ref "R108") (pin "2") (pinfunction "2_2") (pintype "passive"))
    )
    (net (code "47") (name "Net-(LED3-C)") (class "Default")
      (node (ref "LED3") (pin "K") (pinfunction "C_K") (pintype "passive"))
      (node (ref "R105") (pin "2") (pinfunction "2_2") (pintype "passive"))
    )
    (net (code "48") (name "Net-(LED4-PadA)") (class "Default")
      (node (ref "LED4") (pin "A") (pinfunction "A_A") (pintype "passive"))
      (node (ref "R106") (pin "2") (pinfunction "2_2") (pintype "passive"))
    )
    (net (code "49") (name "Net-(LED5-C)") (class "Default")
      (node (ref "LED5") (pin "K") (pinfunction "C_K") (pintype "passive"))
      (node (ref "R103") (pin "2") (pinfunction "2_2") (pintype "passive"))
    )
    (net (code "50") (name "Net-(LED6-PadA)") (class "Default")
      (node (ref "LED6") (pin "A") (pinfunction "A_A") (pintype "passive"))
      (node (ref "R104") (pin "2") (pinfunction "2_2") (pintype "passive"))
    )
    (net (code "51") (name "Net-(M1-A7)") (class "Default")
      (node (ref "C13") (pin "1") (pinfunction "1_1") (pintype "passive"))
      (node (ref "M1") (pin "J2.5") (pinfunction "A7_J2.5") (pintype "bidirectional"))
      (node (ref "R16") (pin "2") (pinfunction "2_2") (pintype "passive"))
    )
    (net (code "52") (name "Net-(M1-D4)") (class "Default")
      (node (ref "M1") (pin "J1.7") (pinfunction "D4_J1.7") (pintype "bidirectional"))
      (node (ref "TP-D1") (pin "TP") (pinfunction "TP_TP") (pintype "input"))
    )
    (net (code "53") (name "Net-(PWRA-KL)") (class "Default")
      (node (ref "PWR") (pin "1") (pinfunction "KL_1") (pintype "passive"))
      (node (ref "U$100") (pin "COM") (pinfunction "COM_COM") (pintype "bidirectional"))
    )
    (net (code "54") (name "Net-(PWRB-KL)") (class "Default")
      (node (ref "F2") (pin "2") (pinfunction "2_2") (pintype "passive"))
      (node (ref "PWR") (pin "2") (pinfunction "KL_2") (pintype "passive"))
    )
    (net (code "55") (name "Net-(Q1-PadG)") (class "Default")
      (node (ref "Q1") (pin "G") (pinfunction "G_G") (pintype "passive"))
      (node (ref "R2") (pin "1") (pinfunction "1_1") (pintype "passive"))
    )
    (net (code "56") (name "Net-(Q2-PadG)") (class "Default")
      (node (ref "Q2") (pin "G") (pinfunction "G_G") (pintype "passive"))
      (node (ref "R4") (pin "1") (pinfunction "1_1") (pintype "passive"))
    )
    (net (code "57") (name "Net-(Q3-PadG)") (class "Default")
      (node (ref "Q3") (pin "G") (pinfunction "G_G") (pintype "passive"))
      (node (ref "R6") (pin "1") (pinfunction "1_1") (pintype "passive"))
    )
    (net (code "58") (name "Net-(Q4-PadG)") (class "Default")
      (node (ref "Q4") (pin "G") (pinfunction "G_G") (pintype "passive"))
      (node (ref "R1") (pin "1") (pinfunction "1_1") (pintype "passive"))
    )
    (net (code "59") (name "Net-(Q5-PadG)") (class "Default")
      (node (ref "Q5") (pin "G") (pinfunction "G_G") (pintype "passive"))
      (node (ref "R3") (pin "1") (pinfunction "1_1") (pintype "passive"))
    )
    (net (code "60") (name "Net-(Q6-PadG)") (class "Default")
      (node (ref "Q6") (pin "G") (pinfunction "G_G") (pintype "passive"))
      (node (ref "R5") (pin "1") (pinfunction "1_1") (pintype "passive"))
    )
    (net (code "61") (name "Net-(R16-Pad1)") (class "Default")
      (node (ref "R16") (pin "1") (pinfunction "1_1") (pintype "passive"))
      (node (ref "R17") (pin "1") (pinfunction "1_1") (pintype "passive"))
      (node (ref "VEL-TRIM") (pin "2") (pinfunction "2_2") (pintype "passive"))
    )
    (net (code "62") (name "PHASE_A") (class "Default")
      (node (ref "C10") (pin "1") (pinfunction "1_1") (pintype "passive"))
      (node (ref "M1") (pin "J2.12") (pinfunction "A0_J2.12") (pintype "bidirectional"))
      (node (ref "R13") (pin "1") (pinfunction "1_1") (pintype "passive"))
    )
    (net (code "63") (name "PHASE_B") (class "Default")
      (node (ref "C11") (pin "1") (pinfunction "1_1") (pintype "passive"))
      (node (ref "M1") (pin "J2.11") (pinfunction "A1_J2.11") (pintype "bidirectional"))
      (node (ref "R14") (pin "1") (pinfunction "1_1") (pintype "passive"))
    )
    (net (code "64") (name "PHASE_C") (class "Default")
      (node (ref "C12") (pin "1") (pinfunction "1_1") (pintype "passive"))
      (node (ref "M1") (pin "J2.10") (pinfunction "A2_J2.10") (pintype "bidirectional"))
      (node (ref "R15") (pin "1") (pinfunction "1_1") (pintype "passive"))
    )
    (net (code "65") (name "PWM_A") (class "Default")
      (node (ref "IC1") (pin "2") (pinfunction "IN_2") (pintype "input"))
      (node (ref "M1") (pin "J1.12") (pinfunction "D9_J1.12") (pintype "bidirectional"))
    )
    (net (code "66") (name "PWM_B") (class "Default")
      (node (ref "IC2") (pin "2") (pinfunction "IN_2") (pintype "input"))
      (node (ref "M1") (pin "J1.13") (pinfunction "D10_J1.13") (pintype "bidirectional"))
    )
    (net (code "67") (name "PWM_C") (class "Default")
      (node (ref "IC3") (pin "2") (pinfunction "IN_2") (pintype "input"))
      (node (ref "M1") (pin "J1.14") (pinfunction "D11/MOSI_J1.14") (pintype "bidirectional"))
    )
    (net (code "68") (name "RESET") (class "Default")
      (node (ref "J1") (pin "P$1") (pinfunction "DTR_P$1") (pintype "passive"))
      (node (ref "M1") (pin "J1.3") (pinfunction "RST.1_J1.3") (pintype "bidirectional"))
    )
    (net (code "69") (name "RXD") (class "Default")
      (node (ref "JP1") (pin "1") (pinfunction "1_1") (pintype "passive"))
      (node (ref "M1") (pin "J1.2") (pinfunction "D0/RX_J1.2") (pintype "bidirectional"))
    )
    (net (code "70") (name "TXD") (class "Default")
      (node (ref "JP1") (pin "3") (pinfunction "3_3") (pintype "passive"))
      (node (ref "M1") (pin "J1.1") (pinfunction "D1/TX_J1.1") (pintype "bidirectional"))
    )
    (net (code "71") (name "V+") (class "Default")
      (node (ref "F1") (pin "2") (pinfunction "2_2") (pintype "passive"))
      (node (ref "F2") (pin "1") (pinfunction "1_1") (pintype "passive"))
      (node (ref "IC4") (pin "1") (pinfunction "IP+_1") (pintype "passive"))
      (node (ref "IC4") (pin "2") (pinfunction "IP+1_2") (pintype "passive"))
      (node (ref "U$14") (pin "N2") (pinfunction "P$2_N2") (pintype "bidirectional"))
    )
    (net (code "72") (name "VCCINT") (class "Default")
      (node (ref "R104") (pin "1") (pinfunction "1_1") (pintype "passive"))
      (node (ref "R106") (pin "1") (pinfunction "1_1") (pintype "passive"))
      (node (ref "R108") (pin "1") (pinfunction "1_1") (pintype "passive"))
      (node (ref "U$14") (pin "N1") (pinfunction "P$1_N1") (pintype "bidirectional"))
    )
    (net (code "73") (name "VDD") (class "Default")
      (node (ref "C4") (pin "+") (pinfunction "+_+") (pintype "passive"))
      (node (ref "C5") (pin "+") (pinfunction "+_+") (pintype "passive"))
      (node (ref "C6") (pin "+") (pinfunction "+_+") (pintype "passive"))
      (node (ref "IC4") (pin "3") (pinfunction "IP-_3") (pintype "passive"))
      (node (ref "IC4") (pin "4") (pinfunction "IP-1_4") (pintype "passive"))
      (node (ref "Q4") (pin "D") (pinfunction "D_D") (pintype "passive"))
      (node (ref "Q5") (pin "D") (pinfunction "D_D") (pintype "passive"))
      (node (ref "Q6") (pin "D") (pinfunction "D_D") (pintype "passive"))
    )
    (net (code "74") (name "VSS") (class "Default")
      (node (ref "C4") (pin "-") (pinfunction "-_-") (pintype "passive"))
      (node (ref "C5") (pin "-") (pinfunction "-_-") (pintype "passive"))
      (node (ref "C6") (pin "-") (pinfunction "-_-") (pintype "passive"))
      (node (ref "C7") (pin "-") (pinfunction "-_-") (pintype "passive"))
      (node (ref "C8") (pin "-") (pinfunction "-_-") (pintype "passive"))
      (node (ref "C9") (pin "-") (pinfunction "-_-") (pintype "passive"))
      (node (ref "IC1") (pin "4") (pinfunction "COM_4") (pintype "power_in"))
      (node (ref "IC2") (pin "4") (pinfunction "COM_4") (pintype "power_in"))
      (node (ref "IC3") (pin "4") (pinfunction "COM_4") (pintype "power_in"))
      (node (ref "Q1") (pin "S") (pinfunction "S_S") (pintype "passive"))
      (node (ref "Q2") (pin "S") (pinfunction "S_S") (pintype "passive"))
      (node (ref "Q3") (pin "S") (pinfunction "S_S") (pintype "passive"))
      (node (ref "R103") (pin "1") (pinfunction "1_1") (pintype "passive"))
      (node (ref "R105") (pin "1") (pinfunction "1_1") (pintype "passive"))
      (node (ref "R107") (pin "1") (pinfunction "1_1") (pintype "passive"))
      (node (ref "R7") (pin "1") (pinfunction "1_1") (pintype "passive"))
      (node (ref "R8") (pin "1") (pinfunction "1_1") (pintype "passive"))
      (node (ref "R9") (pin "1") (pinfunction "1_1") (pintype "passive"))
      (node (ref "U$100") (pin "S1") (pinfunction "S1_S1") (pintype "bidirectional"))
    )
    (net (code "75") (name "unconnected-(J1-CTS-PadP$5)") (class "Default")
      (node (ref "J1") (pin "P$5") (pinfunction "CTS_P$5") (pintype "passive"))
    )
    (net (code "76") (name "unconnected-(M1-AREF-PadJ2.13)") (class "Default")
      (node (ref "M1") (pin "J2.13") (pinfunction "AREF_J2.13") (pintype "bidirectional"))
    )
    (net (code "77") (name "unconnected-(M1-D2-PadJ1.5)") (class "Default")
      (node (ref "M1") (pin "J1.5") (pinfunction "D2_J1.5") (pintype "bidirectional"))
    )
    (net (code "78") (name "unconnected-(M1-D3-PadJ1.6)") (class "Default")
      (node (ref "M1") (pin "J1.6") (pinfunction "D3_J1.6") (pintype "bidirectional"))
    )
    (net (code "79") (name "unconnected-(M1-D5-PadJ1.8)") (class "Default")
      (node (ref "M1") (pin "J1.8") (pinfunction "D5_J1.8") (pintype "bidirectional"))
    )
    (net (code "80") (name "unconnected-(M1-D6-PadJ1.9)") (class "Default")
      (node (ref "M1") (pin "J1.9") (pinfunction "D6_J1.9") (pintype "bidirectional"))
    )
    (net (code "81") (name "unconnected-(M1-D13{slash}SCK-PadJ2.15)") (class "Default")
      (node (ref "M1") (pin "J2.15") (pinfunction "D13/SCK_J2.15") (pintype "bidirectional"))
    )
    (net (code "82") (name "unconnected-(M1-RST.2-PadJ2.3)") (class "Default")
      (node (ref "M1") (pin "J2.3") (pinfunction "RST.2_J2.3") (pintype "bidirectional"))
    )
  )
)
